# ATmega_3000_14.net
KiCad netlist of a schematic drawn in Altium Designer
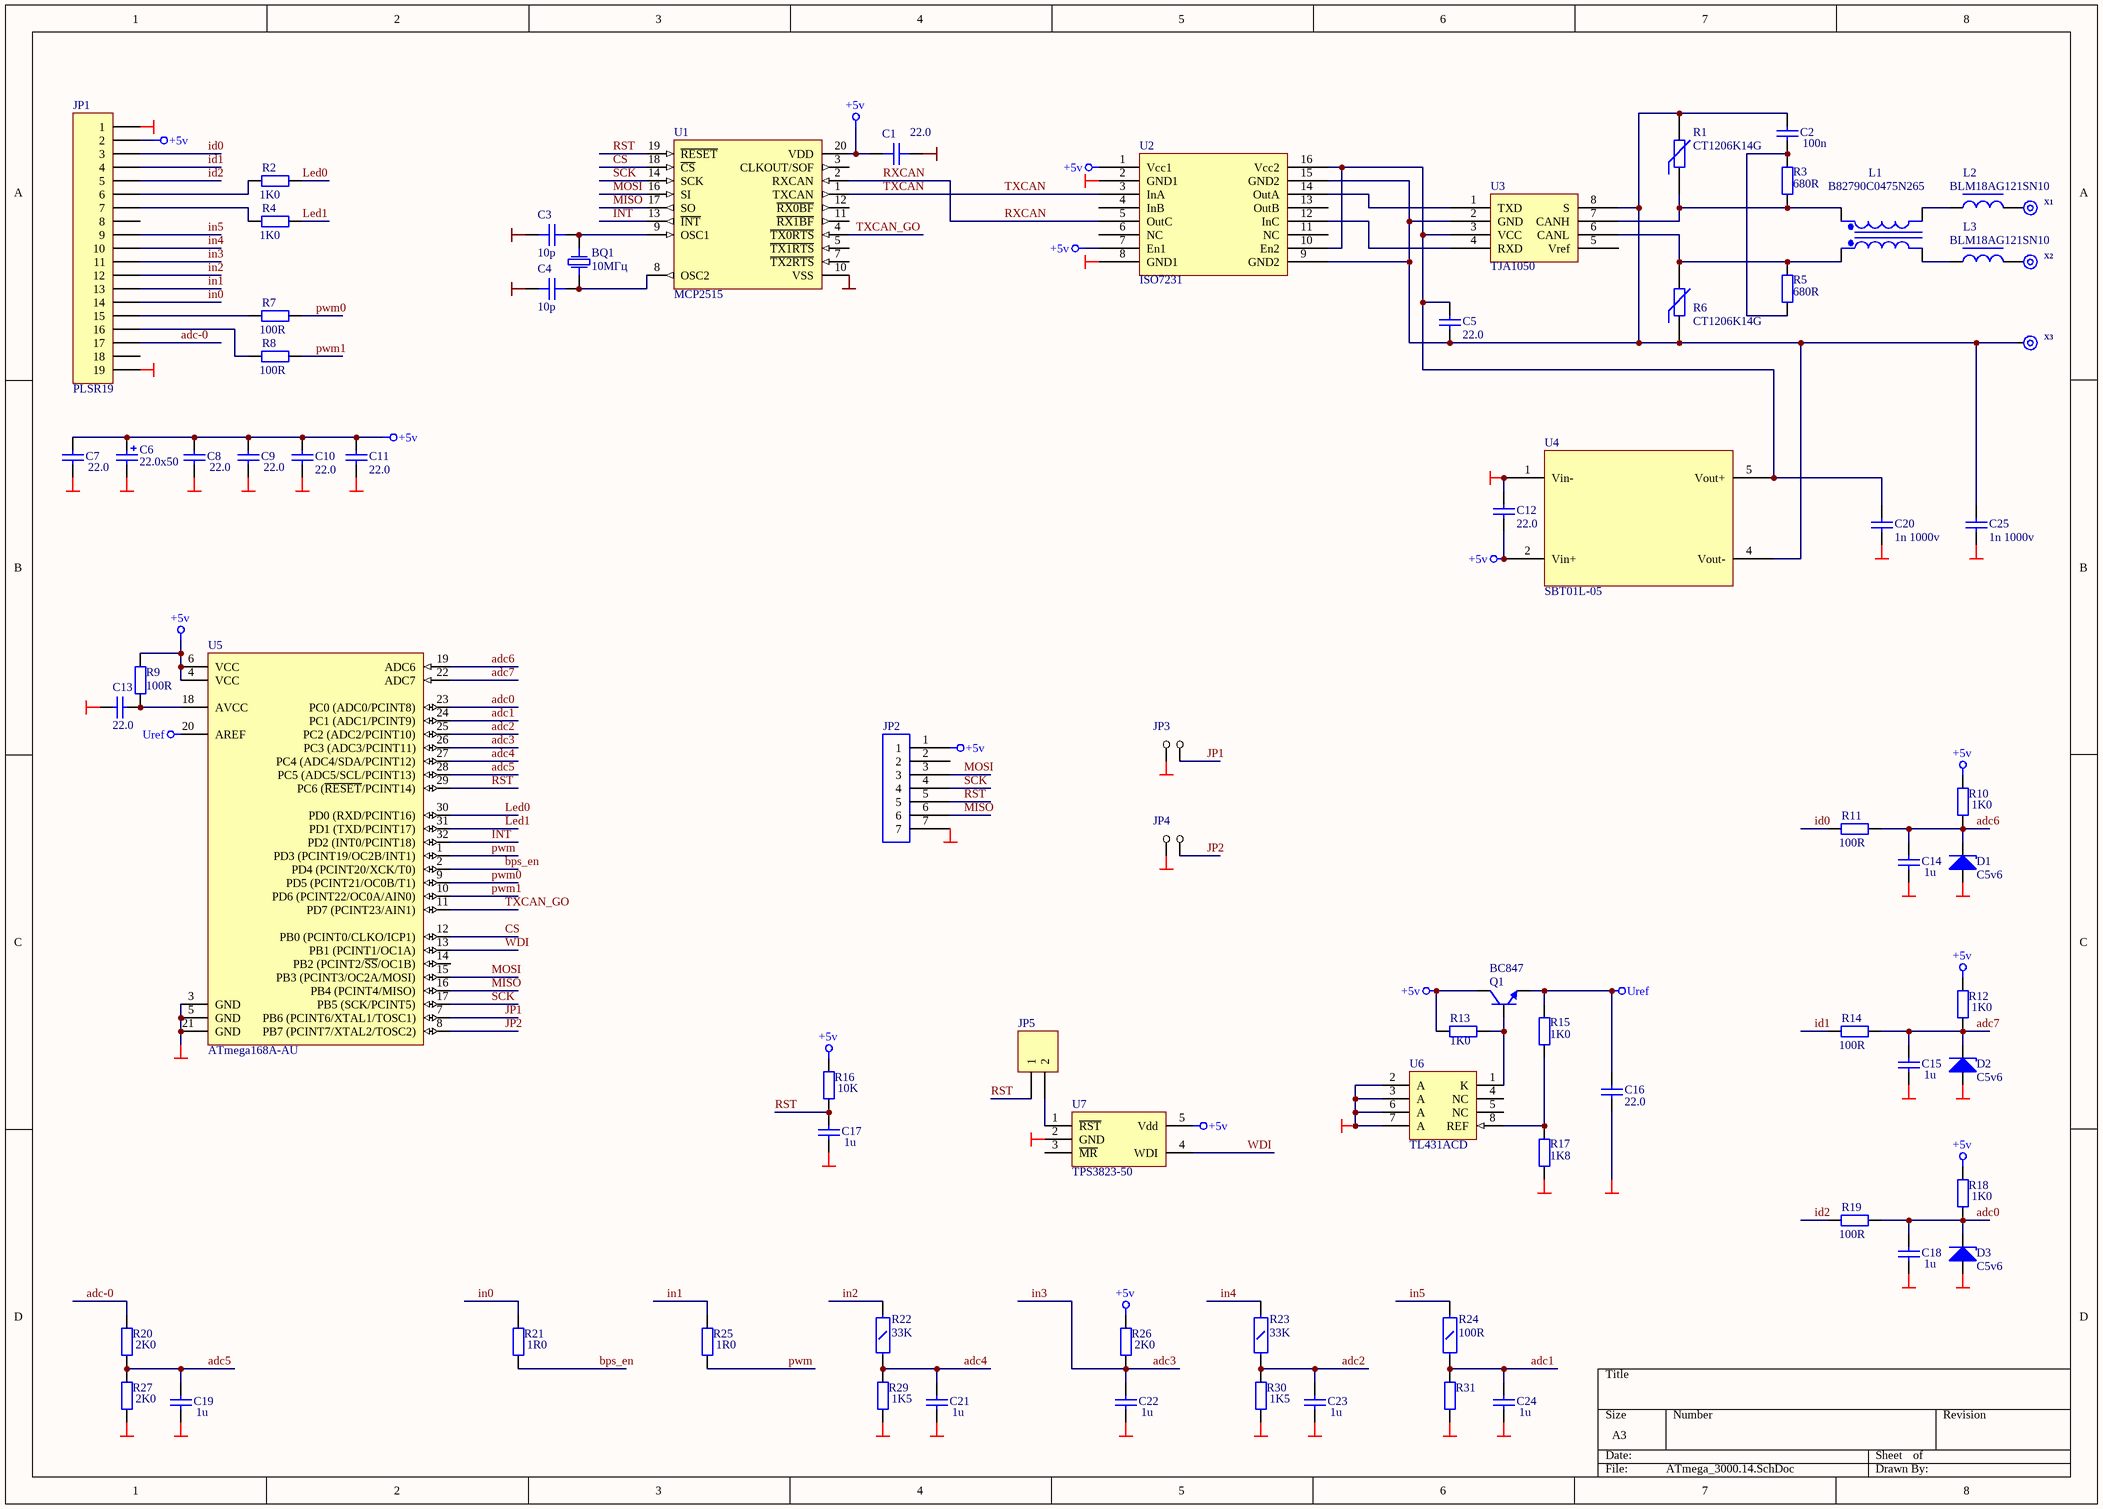
[diagram p0: ATmega_3000.14.SchDoc]

(export (version "E")
  (design (tool "Eeschema 10.0.6"))
  (components
    (comp (ref "BQ1") (value "10МГц") (footprint "HC-49SMD") (libsource (lib "L") (part "BQ")))
    (comp (ref "C1") (value "22.0") (footprint "C_1206") (libsource (lib "C") (part "C_SM_1206")))
    (comp (ref "C2")
      (value "100n")
      (footprint "0603")
      (description "Capacitor (Semiconductor SIM Model)")
      (fields (field (name "MANUFACTURER") "Generic Components") (field (name "PUBLISHER") "Altium Limited"))
      (libsource (lib "Miscellaneous Devices") (part "Cap Semi"))
    )
    (comp (ref "C3") (value "10p") (footprint "0603") (libsource (lib "C") (part "C_SM_1206")))
    (comp (ref "C4") (value "10p") (footprint "0603") (libsource (lib "C") (part "C_SM_1206")))
    (comp (ref "C5")
      (value "22.0")
      (footprint "_1206")
      (description "Capacitor (Semiconductor SIM Model)")
      (fields (field (name "MANUFACTURER") "Generic Components") (field (name "PUBLISHER") "Altium Limited"))
      (libsource (lib "Miscellaneous Devices") (part "Cap Semi"))
    )
    (comp (ref "C6")
      (value "22.0x50")
      (footprint "C_5d_2pad")
      (description "Polarized Capacitor (Radial)")
      (fields (field (name "MANUFACTURER") "Generic Components") (field (name "PUBLISHER") "Altium Limited"))
      (libsource (lib "PAL") (part "Cap Pol1"))
    )
    (comp (ref "C7")
      (value "22.0")
      (footprint "_1206")
      (description "Capacitor (Semiconductor SIM Model)")
      (fields (field (name "MANUFACTURER") "Generic Components") (field (name "PUBLISHER") "Altium Limited"))
      (libsource (lib "Miscellaneous Devices") (part "Cap Semi"))
    )
    (comp (ref "C8")
      (value "22.0")
      (footprint "_1206")
      (description "Capacitor (Semiconductor SIM Model)")
      (fields (field (name "MANUFACTURER") "Generic Components") (field (name "PUBLISHER") "Altium Limited"))
      (libsource (lib "Miscellaneous Devices") (part "Cap Semi"))
    )
    (comp (ref "C9")
      (value "22.0")
      (footprint "_1206")
      (description "Capacitor (Semiconductor SIM Model)")
      (fields (field (name "MANUFACTURER") "Generic Components") (field (name "PUBLISHER") "Altium Limited"))
      (libsource (lib "Miscellaneous Devices") (part "Cap Semi"))
    )
    (comp (ref "C10")
      (value "22.0")
      (footprint "_1206")
      (description "Capacitor (Semiconductor SIM Model)")
      (fields (field (name "MANUFACTURER") "Generic Components") (field (name "PUBLISHER") "Altium Limited"))
      (libsource (lib "Miscellaneous Devices") (part "Cap Semi"))
    )
    (comp (ref "C11")
      (value "22.0")
      (footprint "_1206")
      (description "Capacitor (Semiconductor SIM Model)")
      (fields (field (name "MANUFACTURER") "Generic Components") (field (name "PUBLISHER") "Altium Limited"))
      (libsource (lib "Miscellaneous Devices") (part "Cap Semi"))
    )
    (comp (ref "C12")
      (value "22.0")
      (footprint "_1206")
      (description "Capacitor (Semiconductor SIM Model)")
      (fields (field (name "MANUFACTURER") "Generic Components") (field (name "PUBLISHER") "Altium Limited"))
      (libsource (lib "Miscellaneous Devices") (part "Cap Semi"))
    )
    (comp (ref "C13")
      (value "22.0")
      (footprint "_1206")
      (description "Capacitor (Semiconductor SIM Model)")
      (fields (field (name "MANUFACTURER") "Generic Components") (field (name "PUBLISHER") "Altium Limited"))
      (libsource (lib "Miscellaneous Devices") (part "Cap Semi"))
    )
    (comp (ref "C14")
      (value "1u")
      (footprint "0603")
      (description "Capacitor (Semiconductor SIM Model)")
      (fields (field (name "MANUFACTURER") "Generic Components") (field (name "PUBLISHER") "Altium Limited"))
      (libsource (lib "Miscellaneous Devices") (part "Cap Semi"))
    )
    (comp (ref "C15")
      (value "1u")
      (footprint "0603")
      (description "Capacitor (Semiconductor SIM Model)")
      (fields (field (name "MANUFACTURER") "Generic Components") (field (name "PUBLISHER") "Altium Limited"))
      (libsource (lib "Miscellaneous Devices") (part "Cap Semi"))
    )
    (comp (ref "C16")
      (value "22.0")
      (footprint "_1206")
      (description "Capacitor (Semiconductor SIM Model)")
      (fields (field (name "MANUFACTURER") "Generic Components") (field (name "PUBLISHER") "Altium Limited"))
      (libsource (lib "Miscellaneous Devices") (part "Cap Semi"))
    )
    (comp (ref "C17")
      (value "1u")
      (footprint "0603")
      (description "Capacitor (Semiconductor SIM Model)")
      (fields (field (name "MANUFACTURER") "Generic Components") (field (name "PUBLISHER") "Altium Limited"))
      (libsource (lib "Miscellaneous Devices") (part "Cap Semi"))
    )
    (comp (ref "C18")
      (value "1u")
      (footprint "0603")
      (description "Capacitor (Semiconductor SIM Model)")
      (fields (field (name "MANUFACTURER") "Generic Components") (field (name "PUBLISHER") "Altium Limited"))
      (libsource (lib "Miscellaneous Devices") (part "Cap Semi"))
    )
    (comp (ref "C19")
      (value "1u")
      (footprint "0603")
      (description "Capacitor (Semiconductor SIM Model)")
      (fields (field (name "MANUFACTURER") "Generic Components") (field (name "PUBLISHER") "Altium Limited"))
      (libsource (lib "Miscellaneous Devices") (part "Cap Semi"))
    )
    (comp (ref "C20")
      (value "1n 1000v")
      (footprint "_1206")
      (description "Capacitor (Semiconductor SIM Model)")
      (fields (field (name "MANUFACTURER") "Generic Components") (field (name "PUBLISHER") "Altium Limited"))
      (libsource (lib "Miscellaneous Devices") (part "Cap Semi"))
    )
    (comp (ref "C21")
      (value "1u")
      (footprint "0603")
      (description "Capacitor (Semiconductor SIM Model)")
      (fields (field (name "MANUFACTURER") "Generic Components") (field (name "PUBLISHER") "Altium Limited"))
      (libsource (lib "Miscellaneous Devices") (part "Cap Semi"))
    )
    (comp (ref "C22")
      (value "1u")
      (footprint "0603")
      (description "Capacitor (Semiconductor SIM Model)")
      (fields (field (name "MANUFACTURER") "Generic Components") (field (name "PUBLISHER") "Altium Limited"))
      (libsource (lib "Miscellaneous Devices") (part "Cap Semi"))
    )
    (comp (ref "C23")
      (value "1u")
      (footprint "0603")
      (description "Capacitor (Semiconductor SIM Model)")
      (fields (field (name "MANUFACTURER") "Generic Components") (field (name "PUBLISHER") "Altium Limited"))
      (libsource (lib "Miscellaneous Devices") (part "Cap Semi"))
    )
    (comp (ref "C24")
      (value "1u")
      (footprint "0603")
      (description "Capacitor (Semiconductor SIM Model)")
      (fields (field (name "MANUFACTURER") "Generic Components") (field (name "PUBLISHER") "Altium Limited"))
      (libsource (lib "Miscellaneous Devices") (part "Cap Semi"))
    )
    (comp (ref "C25")
      (value "1n 1000v")
      (footprint "_1206")
      (description "Capacitor (Semiconductor SIM Model)")
      (fields (field (name "MANUFACTURER") "Generic Components") (field (name "PUBLISHER") "Altium Limited"))
      (libsource (lib "Miscellaneous Devices") (part "Cap Semi"))
    )
    (comp (ref "D1")
      (value "C5v6")
      (footprint "SM/D_1406")
      (description "Default Diode")
      (fields (field (name "MANUFACTURER") "Generic Components") (field (name "PUBLISHER") "Altium Limited"))
      (libsource (lib "PAL") (part "Zener"))
    )
    (comp (ref "D2")
      (value "C5v6")
      (footprint "SM/D_1406")
      (description "Default Diode")
      (fields (field (name "MANUFACTURER") "Generic Components") (field (name "PUBLISHER") "Altium Limited"))
      (libsource (lib "PAL") (part "Zener"))
    )
    (comp (ref "D3")
      (value "C5v6")
      (footprint "SM/D_1406")
      (description "Default Diode")
      (fields (field (name "MANUFACTURER") "Generic Components") (field (name "PUBLISHER") "Altium Limited"))
      (libsource (lib "PAL") (part "Zener"))
    )
    (comp (ref "JP1")
      (value "PLSR19")
      (footprint "HDR1X19")
      (description "Header, 19-Pin")
      (fields (field (name "MANUFACTURER") "Generic Components") (field (name "PUBLISHER") "Altium Limited"))
      (libsource (lib "Miscellaneous Connectors") (part "Header 19"))
    )
    (comp (ref "JP2") (value "PLSF-7") (footprint "HDR1X7") (libsource (lib "RAZJEM") (part "PLSF-7")))
    (comp (ref "JP3") (value "JMP") (footprint "HDR1X2") (libsource (lib "RAZJEM") (part "JMP")))
    (comp (ref "JP4") (value "JMP") (footprint "HDR1X2") (libsource (lib "RAZJEM") (part "JMP")))
    (comp (ref "JP5")
      (value "PLS2")
      (footprint "HDR1X2")
      (description "Header, 2-Pin")
      (fields (field (name "MANUFACTURER") "Generic Components") (field (name "PUBLISHER") "Altium Limited"))
      (libsource (lib "Miscellaneous Connectors") (part "Header 2"))
    )
    (comp (ref "L1")
      (value "B82790C0475N265")
      (footprint "B82790")
      (description "Transformer (Coupled Inductor Model)")
      (fields (field (name "PUBLISHER") "Altium Limited"))
      (libsource (lib "Miscellaneous Devices") (part "Trans Cupl"))
    )
    (comp (ref "L2")
      (value "BLM18AG121SN10")
      (footprint "0603")
      (description "L")
      (libsource (lib "L") (part "DR"))
    )
    (comp (ref "L3")
      (value "BLM18AG121SN10")
      (footprint "0603")
      (description "L")
      (libsource (lib "L") (part "DR"))
    )
    (comp (ref "Q1")
      (value "BC847")
      (footprint "SOT23")
      (description "General Purpose Transistor NPN Silicon")
      (fields (field (name "MANUFACTURER") "Motorola") (field (name "PUBLISHER") "Altium Limited"))
      (libsource (lib "PAL") (part "BC847ALT1"))
    )
    (comp (ref "R1")
      (value "CT1206K14G")
      (footprint "1206")
      (description "Varistor (Voltage-Sensitive Resistor)")
      (fields (field (name "MANUFACTURER") "Generic Components") (field (name "PUBLISHER") "Altium Limited"))
      (libsource (lib "Miscellaneous Devices") (part "Res Varistor"))
    )
    (comp (ref "R2")
      (value "1K0")
      (footprint "0603")
      (description "Resistor")
      (fields (field (name "MANUFACTURER") "Generic Components") (field (name "PUBLISHER") "Altium Limited"))
      (libsource (lib "") (part "Res2_2"))
    )
    (comp (ref "R3")
      (value "680R")
      (footprint "0603")
      (description "Resistor")
      (fields (field (name "MANUFACTURER") "Generic Components") (field (name "PUBLISHER") "Altium Limited"))
      (libsource (lib "") (part "Res2_2"))
    )
    (comp (ref "R4")
      (value "1K0")
      (footprint "0603")
      (description "Resistor")
      (fields (field (name "MANUFACTURER") "Generic Components") (field (name "PUBLISHER") "Altium Limited"))
      (libsource (lib "") (part "Res2_2"))
    )
    (comp (ref "R5")
      (value "680R")
      (footprint "0603")
      (description "Resistor")
      (fields (field (name "MANUFACTURER") "Generic Components") (field (name "PUBLISHER") "Altium Limited"))
      (libsource (lib "") (part "Res2_2"))
    )
    (comp (ref "R6")
      (value "CT1206K14G")
      (footprint "1206")
      (description "Varistor (Voltage-Sensitive Resistor)")
      (fields (field (name "MANUFACTURER") "Generic Components") (field (name "PUBLISHER") "Altium Limited"))
      (libsource (lib "Miscellaneous Devices") (part "Res Varistor"))
    )
    (comp (ref "R7")
      (value "100R")
      (footprint "0603")
      (description "Resistor")
      (fields (field (name "MANUFACTURER") "Generic Components") (field (name "PUBLISHER") "Altium Limited"))
      (libsource (lib "") (part "Res2_1"))
    )
    (comp (ref "R8")
      (value "100R")
      (footprint "0603")
      (description "Resistor")
      (fields (field (name "MANUFACTURER") "Generic Components") (field (name "PUBLISHER") "Altium Limited"))
      (libsource (lib "") (part "Res2_1"))
    )
    (comp (ref "R9")
      (value "100R")
      (footprint "0603")
      (description "Resistor")
      (fields (field (name "MANUFACTURER") "Generic Components") (field (name "PUBLISHER") "Altium Limited"))
      (libsource (lib "") (part "Res2_4"))
    )
    (comp (ref "R10")
      (value "1K0")
      (footprint "0603")
      (description "Resistor")
      (fields (field (name "MANUFACTURER") "Generic Components") (field (name "PUBLISHER") "Altium Limited"))
      (libsource (lib "") (part "Res2_3"))
    )
    (comp (ref "R11")
      (value "100R")
      (footprint "0603")
      (description "Resistor")
      (fields (field (name "MANUFACTURER") "Generic Components") (field (name "PUBLISHER") "Altium Limited"))
      (libsource (lib "") (part "Res2_1"))
    )
    (comp (ref "R12")
      (value "1K0")
      (footprint "0603")
      (description "Resistor")
      (fields (field (name "MANUFACTURER") "Generic Components") (field (name "PUBLISHER") "Altium Limited"))
      (libsource (lib "") (part "Res2_3"))
    )
    (comp (ref "R13")
      (value "1K0")
      (footprint "0603")
      (description "Resistor")
      (fields (field (name "MANUFACTURER") "Generic Components") (field (name "PUBLISHER") "Altium Limited"))
      (libsource (lib "") (part "Res2_5"))
    )
    (comp (ref "R14")
      (value "100R")
      (footprint "0603")
      (description "Resistor")
      (fields (field (name "MANUFACTURER") "Generic Components") (field (name "PUBLISHER") "Altium Limited"))
      (libsource (lib "") (part "Res2_1"))
    )
    (comp (ref "R15")
      (value "1K0")
      (footprint "0603")
      (description "Resistor")
      (fields (field (name "MANUFACTURER") "Generic Components") (field (name "PUBLISHER") "Altium Limited"))
      (libsource (lib "") (part "Res2_2"))
    )
    (comp (ref "R16")
      (value "10K")
      (footprint "0603")
      (description "Resistor")
      (fields (field (name "MANUFACTURER") "Generic Components") (field (name "PUBLISHER") "Altium Limited"))
      (libsource (lib "") (part "Res2_3"))
    )
    (comp (ref "R17")
      (value "1K8")
      (footprint "0603")
      (description "Resistor")
      (fields (field (name "MANUFACTURER") "Generic Components") (field (name "PUBLISHER") "Altium Limited"))
      (libsource (lib "") (part "Res2_2"))
    )
    (comp (ref "R18")
      (value "1K0")
      (footprint "0603")
      (description "Resistor")
      (fields (field (name "MANUFACTURER") "Generic Components") (field (name "PUBLISHER") "Altium Limited"))
      (libsource (lib "") (part "Res2_3"))
    )
    (comp (ref "R19")
      (value "100R")
      (footprint "0603")
      (description "Resistor")
      (fields (field (name "MANUFACTURER") "Generic Components") (field (name "PUBLISHER") "Altium Limited"))
      (libsource (lib "") (part "Res2_1"))
    )
    (comp (ref "R20")
      (value "2K0")
      (footprint "0603")
      (description "Resistor")
      (fields (field (name "MANUFACTURER") "Generic Components") (field (name "PUBLISHER") "Altium Limited"))
      (libsource (lib "Miscellaneous Devices") (part "Res2"))
    )
    (comp (ref "R21")
      (value "1R0")
      (footprint "0603")
      (description "Resistor")
      (fields (field (name "MANUFACTURER") "Generic Components") (field (name "PUBLISHER") "Altium Limited"))
      (libsource (lib "Miscellaneous Devices") (part "Res2"))
    )
    (comp (ref "R22") (value "33K") (footprint "1206") (libsource (lib "resistor") (part "R_1206")))
    (comp (ref "R23") (value "33K") (footprint "1206") (libsource (lib "resistor") (part "R_1206")))
    (comp (ref "R24") (value "100R") (footprint "1206") (libsource (lib "resistor") (part "R_1206")))
    (comp (ref "R25")
      (value "1R0")
      (footprint "0603")
      (description "Resistor")
      (fields (field (name "MANUFACTURER") "Generic Components") (field (name "PUBLISHER") "Altium Limited"))
      (libsource (lib "Miscellaneous Devices") (part "Res2"))
    )
    (comp (ref "R26")
      (value "2K0")
      (footprint "0603")
      (description "Resistor")
      (fields (field (name "MANUFACTURER") "Generic Components") (field (name "PUBLISHER") "Altium Limited"))
      (libsource (lib "Miscellaneous Devices") (part "Res2"))
    )
    (comp (ref "R27")
      (value "2K0")
      (footprint "0603")
      (description "Resistor")
      (fields (field (name "MANUFACTURER") "Generic Components") (field (name "PUBLISHER") "Altium Limited"))
      (libsource (lib "Miscellaneous Devices") (part "Res2"))
    )
    (comp (ref "R29")
      (value "1K5")
      (footprint "0603")
      (description "Resistor")
      (fields (field (name "MANUFACTURER") "Generic Components") (field (name "PUBLISHER") "Altium Limited"))
      (libsource (lib "Miscellaneous Devices") (part "Res2"))
    )
    (comp (ref "R30")
      (value "1K5")
      (footprint "0603")
      (description "Resistor")
      (fields (field (name "MANUFACTURER") "Generic Components") (field (name "PUBLISHER") "Altium Limited"))
      (libsource (lib "Miscellaneous Devices") (part "Res2"))
    )
    (comp (ref "R31")
      (value "~")
      (footprint "0603")
      (description "Resistor")
      (fields (field (name "MANUFACTURER") "Generic Components") (field (name "PUBLISHER") "Altium Limited"))
      (libsource (lib "Miscellaneous Devices") (part "Res2"))
    )
    (comp (ref "U1")
      (value "MCP2515")
      (footprint "TSSOP-ST20_N")
      (description "Stand-Alone CAN Controller With SPI Interface, 20-Pin TSSOP, Industrial Temperature")
      (libsource (lib "CHIP") (part "MCP2515"))
    )
    (comp (ref "U2") (value "ISO7231") (footprint "DW16_N") (libsource (lib "PAL") (part "ISO7231")))
    (comp (ref "U3")
      (value "TJA1050")
      (footprint "SOIC-8-1.27-L.200")
      (libsource (lib "PAL") (part "TJA1050"))
    )
    (comp (ref "U4") (value "SBT01L-05") (footprint "SBT01L") (libsource (lib "PAL") (part "SBT01L")))
    (comp (ref "U5")
      (value "ATmega168A-AU")
      (footprint "32A_N")
      (fields (field (name "PUBLISHER") "Altium Limited"))
      (libsource (lib "Atmel Microcontroller 8-Bit megaAVR") (part "ATmega168A-AU"))
    )
    (comp (ref "U6")
      (value "TL431ACD")
      (footprint "SO-G8")
      (description "Programmable Precision Reference")
      (fields (field (name "MANUFACTURER") "Motorola") (field (name "PUBLISHER") "Altium Limited"))
      (libsource (lib "Motorola Power Management Voltage Reference") (part "TL431ACD"))
    )
    (comp (ref "U7")
      (value "TPS3823-50")
      (footprint "SO-G5/P.95")
      (description "Reset IC")
      (fields
        (field (name "MANUFACTURER") "National Semiconductor")
        (field (name "PUBLISHER") "Altium Limited")
      )
      (libsource (lib "PAL") (part "TPS3823"))
    )
    (comp (ref "X1")
      (value "~")
      (footprint "PIN2R")
      (description "Socket")
      (fields (field (name "MANUFACTURER") "Generic Components") (field (name "PUBLISHER") "Altium Limited"))
      (libsource (lib "PAL") (part "Socket_Ring"))
    )
    (comp (ref "X2")
      (value "~")
      (footprint "PIN2R")
      (description "Socket")
      (fields (field (name "MANUFACTURER") "Generic Components") (field (name "PUBLISHER") "Altium Limited"))
      (libsource (lib "PAL") (part "Socket_Ring"))
    )
    (comp (ref "X3")
      (value "~")
      (footprint "PIN2R")
      (description "Socket")
      (fields (field (name "MANUFACTURER") "Generic Components") (field (name "PUBLISHER") "Altium Limited"))
      (libsource (lib "PAL") (part "Socket_Ring"))
    )
  )
  (nets
    (net (code "1") (name "+5v") (class "Default")
      (node (ref "C1") (pin "2") (pinfunction "2_2") (pintype "passive"))
      (node (ref "C10") (pin "1") (pinfunction "1_1") (pintype "passive"))
      (node (ref "C11") (pin "1") (pinfunction "1_1") (pintype "passive"))
      (node (ref "C12") (pin "2") (pinfunction "2_2") (pintype "passive"))
      (node (ref "C6") (pin "+") (pinfunction "+_+") (pintype "passive"))
      (node (ref "C7") (pin "2") (pinfunction "2_2") (pintype "passive"))
      (node (ref "C8") (pin "2") (pinfunction "2_2") (pintype "passive"))
      (node (ref "C9") (pin "2") (pinfunction "2_2") (pintype "passive"))
      (node (ref "JP1") (pin "2") (pinfunction "2_2") (pintype "passive"))
      (node (ref "JP2") (pin "1") (pinfunction "1_1") (pintype "passive"))
      (node (ref "Q1") (pin "2") (pinfunction "C_2") (pintype "passive"))
      (node (ref "R10") (pin "1") (pinfunction "1_1") (pintype "passive"))
      (node (ref "R12") (pin "1") (pinfunction "1_1") (pintype "passive"))
      (node (ref "R13") (pin "1") (pinfunction "1_1") (pintype "passive"))
      (node (ref "R16") (pin "1") (pinfunction "1_1") (pintype "passive"))
      (node (ref "R18") (pin "1") (pinfunction "1_1") (pintype "passive"))
      (node (ref "R26") (pin "2") (pinfunction "2_2") (pintype "passive"))
      (node (ref "R9") (pin "1") (pinfunction "1_1") (pintype "passive"))
      (node (ref "U1") (pin "20") (pinfunction "VDD_20") (pintype "power_in"))
      (node (ref "U2") (pin "1") (pinfunction "Vcc1_1") (pintype "passive"))
      (node (ref "U2") (pin "7") (pinfunction "En1_7") (pintype "passive"))
      (node (ref "U4") (pin "2") (pinfunction "Vin+_2") (pintype "passive"))
      (node (ref "U5") (pin "4") (pinfunction "VCC_4") (pintype "power_in"))
      (node (ref "U5") (pin "6") (pinfunction "VCC_6") (pintype "power_in"))
      (node (ref "U7") (pin "5") (pinfunction "Vdd_5") (pintype "power_in"))
    )
    (net (code "2") (name "/CS") (class "Default")
      (node (ref "U1") (pin "18") (pinfunction "~{CS}_18") (pintype "input"))
      (node (ref "U5") (pin "12") (pinfunction "PB0_(PCINT0/CLKO/ICP1)_12") (pintype "bidirectional"))
    )
    (net (code "3") (name "/INT") (class "Default")
      (node (ref "U1") (pin "13") (pinfunction "~{INT}_13") (pintype "output"))
      (node (ref "U5") (pin "32") (pinfunction "PD2_(INT0/PCINT18)_32") (pintype "bidirectional"))
    )
    (net (code "4") (name "/JP1") (class "Default")
      (node (ref "JP3") (pin "2") (pinfunction "2_2") (pintype "passive"))
      (node (ref "U5") (pin "7") (pinfunction "PB6_(PCINT6/XTAL1/TOSC1)_7") (pintype "bidirectional"))
    )
    (net (code "5") (name "/JP2") (class "Default")
      (node (ref "JP4") (pin "2") (pinfunction "2_2") (pintype "passive"))
      (node (ref "U5") (pin "8") (pinfunction "PB7_(PCINT7/XTAL2/TOSC2)_8") (pintype "bidirectional"))
    )
    (net (code "6") (name "/Led0") (class "Default")
      (node (ref "R2") (pin "2") (pinfunction "2_2") (pintype "passive"))
      (node (ref "U5") (pin "30") (pinfunction "PD0_(RXD/PCINT16)_30") (pintype "bidirectional"))
    )
    (net (code "7") (name "/Led1") (class "Default")
      (node (ref "R4") (pin "2") (pinfunction "2_2") (pintype "passive"))
      (node (ref "U5") (pin "31") (pinfunction "PD1_(TXD/PCINT17)_31") (pintype "bidirectional"))
    )
    (net (code "8") (name "/MISO") (class "Default")
      (node (ref "JP2") (pin "6") (pinfunction "6_6") (pintype "passive"))
      (node (ref "U1") (pin "17") (pinfunction "SO_17") (pintype "output"))
      (node (ref "U5") (pin "16") (pinfunction "PB4_(PCINT4/MISO)_16") (pintype "bidirectional"))
    )
    (net (code "9") (name "/MOSI") (class "Default")
      (node (ref "JP2") (pin "3") (pinfunction "3_3") (pintype "passive"))
      (node (ref "U1") (pin "16") (pinfunction "SI_16") (pintype "input"))
      (node (ref "U5") (pin "15") (pinfunction "PB3_(PCINT3/OC2A/MOSI)_15") (pintype "bidirectional"))
    )
    (net (code "10") (name "/RST") (class "Default")
      (node (ref "C17") (pin "2") (pinfunction "2_2") (pintype "passive"))
      (node (ref "JP2") (pin "5") (pinfunction "5_5") (pintype "passive"))
      (node (ref "JP5") (pin "1") (pinfunction "1_1") (pintype "passive"))
      (node (ref "R16") (pin "2") (pinfunction "2_2") (pintype "passive"))
      (node (ref "U1") (pin "19") (pinfunction "~{RESET}_19") (pintype "input"))
      (node (ref "U5") (pin "29") (pinfunction "PC6_(~{RESET}/PCINT14)_29") (pintype "bidirectional"))
    )
    (net (code "11") (name "/RXCAN") (class "Default")
      (node (ref "U1") (pin "2") (pinfunction "RXCAN_2") (pintype "input"))
      (node (ref "U2") (pin "5") (pinfunction "OutC_5") (pintype "passive"))
    )
    (net (code "12") (name "/SCK") (class "Default")
      (node (ref "JP2") (pin "4") (pinfunction "4_4") (pintype "passive"))
      (node (ref "U1") (pin "14") (pinfunction "SCK_14") (pintype "input"))
      (node (ref "U5") (pin "17") (pinfunction "PB5_(SCK/PCINT5)_17") (pintype "bidirectional"))
    )
    (net (code "13") (name "/TXCAN") (class "Default")
      (node (ref "U1") (pin "1") (pinfunction "TXCAN_1") (pintype "output"))
      (node (ref "U2") (pin "3") (pinfunction "InA_3") (pintype "passive"))
    )
    (net (code "14") (name "/TXCAN_GO") (class "Default")
      (node (ref "U1") (pin "4") (pinfunction "~{TX0RTS}_4") (pintype "input"))
      (node (ref "U5") (pin "11") (pinfunction "PD7_(PCINT23/AIN1)_11") (pintype "bidirectional"))
    )
    (net (code "15") (name "/WDI") (class "Default")
      (node (ref "U5") (pin "13") (pinfunction "PB1_(PCINT1/OC1A)_13") (pintype "bidirectional"))
      (node (ref "U7") (pin "4") (pinfunction "WDI_4") (pintype "passive"))
    )
    (net (code "16") (name "/adc-0") (class "Default")
      (node (ref "JP1") (pin "17") (pinfunction "17_17") (pintype "passive"))
      (node (ref "R20") (pin "2") (pinfunction "2_2") (pintype "passive"))
    )
    (net (code "17") (name "/adc0") (class "Default")
      (node (ref "C18") (pin "2") (pinfunction "2_2") (pintype "passive"))
      (node (ref "D3") (pin "-") (pinfunction "-_-") (pintype "passive"))
      (node (ref "R18") (pin "2") (pinfunction "2_2") (pintype "passive"))
      (node (ref "R19") (pin "1") (pinfunction "1_1") (pintype "passive"))
      (node (ref "U5") (pin "23") (pinfunction "PC0_(ADC0/PCINT8)_23") (pintype "bidirectional"))
    )
    (net (code "18") (name "/adc1") (class "Default")
      (node (ref "C24") (pin "2") (pinfunction "2_2") (pintype "passive"))
      (node (ref "R24") (pin "2") (pinfunction "2_2") (pintype "passive"))
      (node (ref "R31") (pin "2") (pinfunction "2_2") (pintype "passive"))
      (node (ref "U5") (pin "24") (pinfunction "PC1_(ADC1/PCINT9)_24") (pintype "bidirectional"))
    )
    (net (code "19") (name "/adc2") (class "Default")
      (node (ref "C23") (pin "2") (pinfunction "2_2") (pintype "passive"))
      (node (ref "R23") (pin "2") (pinfunction "2_2") (pintype "passive"))
      (node (ref "R30") (pin "2") (pinfunction "2_2") (pintype "passive"))
      (node (ref "U5") (pin "25") (pinfunction "PC2_(ADC2/PCINT10)_25") (pintype "bidirectional"))
    )
    (net (code "20") (name "/adc3") (class "Default")
      (node (ref "C22") (pin "2") (pinfunction "2_2") (pintype "passive"))
      (node (ref "JP1") (pin "11") (pinfunction "11_11") (pintype "passive"))
      (node (ref "R26") (pin "1") (pinfunction "1_1") (pintype "passive"))
      (node (ref "U5") (pin "26") (pinfunction "PC3_(ADC3/PCINT11)_26") (pintype "bidirectional"))
    )
    (net (code "21") (name "/adc4") (class "Default")
      (node (ref "C21") (pin "2") (pinfunction "2_2") (pintype "passive"))
      (node (ref "R22") (pin "2") (pinfunction "2_2") (pintype "passive"))
      (node (ref "R29") (pin "2") (pinfunction "2_2") (pintype "passive"))
      (node (ref "U5") (pin "27") (pinfunction "PC4_(ADC4/SDA/PCINT12)_27") (pintype "bidirectional"))
    )
    (net (code "22") (name "/adc5") (class "Default")
      (node (ref "C19") (pin "2") (pinfunction "2_2") (pintype "passive"))
      (node (ref "R20") (pin "1") (pinfunction "1_1") (pintype "passive"))
      (node (ref "R27") (pin "2") (pinfunction "2_2") (pintype "passive"))
      (node (ref "U5") (pin "28") (pinfunction "PC5_(ADC5/SCL/PCINT13)_28") (pintype "bidirectional"))
    )
    (net (code "23") (name "/adc6") (class "Default")
      (node (ref "C14") (pin "2") (pinfunction "2_2") (pintype "passive"))
      (node (ref "D1") (pin "-") (pinfunction "-_-") (pintype "passive"))
      (node (ref "R10") (pin "2") (pinfunction "2_2") (pintype "passive"))
      (node (ref "R11") (pin "1") (pinfunction "1_1") (pintype "passive"))
      (node (ref "U5") (pin "19") (pinfunction "ADC6_19") (pintype "input"))
    )
    (net (code "24") (name "/adc7") (class "Default")
      (node (ref "C15") (pin "2") (pinfunction "2_2") (pintype "passive"))
      (node (ref "D2") (pin "-") (pinfunction "-_-") (pintype "passive"))
      (node (ref "R12") (pin "2") (pinfunction "2_2") (pintype "passive"))
      (node (ref "R14") (pin "1") (pinfunction "1_1") (pintype "passive"))
      (node (ref "U5") (pin "22") (pinfunction "ADC7_22") (pintype "input"))
    )
    (net (code "25") (name "/bps_en") (class "Default")
      (node (ref "R21") (pin "1") (pinfunction "1_1") (pintype "passive"))
      (node (ref "U5") (pin "2") (pinfunction "PD4_(PCINT20/XCK/T0)_2") (pintype "bidirectional"))
    )
    (net (code "26") (name "/id0") (class "Default")
      (node (ref "JP1") (pin "3") (pinfunction "3_3") (pintype "passive"))
      (node (ref "R11") (pin "2") (pinfunction "2_2") (pintype "passive"))
    )
    (net (code "27") (name "/id1") (class "Default")
      (node (ref "JP1") (pin "4") (pinfunction "4_4") (pintype "passive"))
      (node (ref "R14") (pin "2") (pinfunction "2_2") (pintype "passive"))
    )
    (net (code "28") (name "/id2") (class "Default")
      (node (ref "JP1") (pin "5") (pinfunction "5_5") (pintype "passive"))
      (node (ref "R19") (pin "2") (pinfunction "2_2") (pintype "passive"))
    )
    (net (code "29") (name "/in0") (class "Default")
      (node (ref "JP1") (pin "14") (pinfunction "14_14") (pintype "passive"))
      (node (ref "R21") (pin "2") (pinfunction "2_2") (pintype "passive"))
    )
    (net (code "30") (name "/in1") (class "Default")
      (node (ref "JP1") (pin "13") (pinfunction "13_13") (pintype "passive"))
      (node (ref "R25") (pin "2") (pinfunction "2_2") (pintype "passive"))
    )
    (net (code "31") (name "/in2") (class "Default")
      (node (ref "JP1") (pin "12") (pinfunction "12_12") (pintype "passive"))
      (node (ref "R22") (pin "1") (pinfunction "1_1") (pintype "passive"))
    )
    (net (code "32") (name "/in4") (class "Default")
      (node (ref "JP1") (pin "10") (pinfunction "10_10") (pintype "passive"))
      (node (ref "R23") (pin "1") (pinfunction "1_1") (pintype "passive"))
    )
    (net (code "33") (name "/in5") (class "Default")
      (node (ref "JP1") (pin "9") (pinfunction "9_9") (pintype "passive"))
      (node (ref "R24") (pin "1") (pinfunction "1_1") (pintype "passive"))
    )
    (net (code "34") (name "/pwm") (class "Default")
      (node (ref "R25") (pin "1") (pinfunction "1_1") (pintype "passive"))
      (node (ref "U5") (pin "1") (pinfunction "PD3_(PCINT19/OC2B/INT1)_1") (pintype "bidirectional"))
    )
    (net (code "35") (name "/pwm0") (class "Default")
      (node (ref "R7") (pin "1") (pinfunction "1_1") (pintype "passive"))
      (node (ref "U5") (pin "9") (pinfunction "PD5_(PCINT21/OC0B/T1)_9") (pintype "bidirectional"))
    )
    (net (code "36") (name "/pwm1") (class "Default")
      (node (ref "R8") (pin "1") (pinfunction "1_1") (pintype "passive"))
      (node (ref "U5") (pin "10") (pinfunction "PD6_(PCINT22/OC0A/AIN0)_10") (pintype "bidirectional"))
    )
    (net (code "37") (name "GND") (class "Default")
      (node (ref "C1") (pin "1") (pinfunction "1_1") (pintype "passive"))
      (node (ref "C10") (pin "2") (pinfunction "2_2") (pintype "passive"))
      (node (ref "C11") (pin "2") (pinfunction "2_2") (pintype "passive"))
      (node (ref "C12") (pin "1") (pinfunction "1_1") (pintype "passive"))
      (node (ref "C13") (pin "1") (pinfunction "1_1") (pintype "passive"))
      (node (ref "C14") (pin "1") (pinfunction "1_1") (pintype "passive"))
      (node (ref "C15") (pin "1") (pinfunction "1_1") (pintype "passive"))
      (node (ref "C16") (pin "1") (pinfunction "1_1") (pintype "passive"))
      (node (ref "C17") (pin "1") (pinfunction "1_1") (pintype "passive"))
      (node (ref "C18") (pin "1") (pinfunction "1_1") (pintype "passive"))
      (node (ref "C19") (pin "1") (pinfunction "1_1") (pintype "passive"))
      (node (ref "C20") (pin "2") (pinfunction "2_2") (pintype "passive"))
      (node (ref "C21") (pin "1") (pinfunction "1_1") (pintype "passive"))
      (node (ref "C22") (pin "1") (pinfunction "1_1") (pintype "passive"))
      (node (ref "C23") (pin "1") (pinfunction "1_1") (pintype "passive"))
      (node (ref "C24") (pin "1") (pinfunction "1_1") (pintype "passive"))
      (node (ref "C25") (pin "2") (pinfunction "2_2") (pintype "passive"))
      (node (ref "C3") (pin "1") (pinfunction "1_1") (pintype "passive"))
      (node (ref "C4") (pin "1") (pinfunction "1_1") (pintype "passive"))
      (node (ref "C6") (pin "-") (pinfunction "-_-") (pintype "passive"))
      (node (ref "C7") (pin "1") (pinfunction "1_1") (pintype "passive"))
      (node (ref "C8") (pin "1") (pinfunction "1_1") (pintype "passive"))
      (node (ref "C9") (pin "1") (pinfunction "1_1") (pintype "passive"))
      (node (ref "D1") (pin "+") (pinfunction "+_+") (pintype "passive"))
      (node (ref "D2") (pin "+") (pinfunction "+_+") (pintype "passive"))
      (node (ref "D3") (pin "+") (pinfunction "+_+") (pintype "passive"))
      (node (ref "JP1") (pin "1") (pinfunction "1_1") (pintype "passive"))
      (node (ref "JP1") (pin "19") (pinfunction "19_19") (pintype "passive"))
      (node (ref "JP2") (pin "7") (pinfunction "7_7") (pintype "passive"))
      (node (ref "JP3") (pin "1") (pinfunction "1_1") (pintype "passive"))
      (node (ref "JP4") (pin "1") (pinfunction "1_1") (pintype "passive"))
      (node (ref "R17") (pin "1") (pinfunction "1_1") (pintype "passive"))
      (node (ref "R27") (pin "1") (pinfunction "1_1") (pintype "passive"))
      (node (ref "R29") (pin "1") (pinfunction "1_1") (pintype "passive"))
      (node (ref "R30") (pin "1") (pinfunction "1_1") (pintype "passive"))
      (node (ref "R31") (pin "1") (pinfunction "1_1") (pintype "passive"))
      (node (ref "U1") (pin "10") (pinfunction "VSS_10") (pintype "power_in"))
      (node (ref "U2") (pin "2") (pinfunction "GND1_2") (pintype "passive"))
      (node (ref "U2") (pin "8") (pinfunction "GND1_8") (pintype "passive"))
      (node (ref "U4") (pin "1") (pinfunction "Vin-_1") (pintype "passive"))
      (node (ref "U5") (pin "21") (pinfunction "GND_21") (pintype "power_in"))
      (node (ref "U5") (pin "3") (pinfunction "GND_3") (pintype "power_in"))
      (node (ref "U5") (pin "5") (pinfunction "GND_5") (pintype "power_in"))
      (node (ref "U6") (pin "2") (pinfunction "A_2") (pintype "passive"))
      (node (ref "U6") (pin "3") (pinfunction "A_3") (pintype "passive"))
      (node (ref "U6") (pin "6") (pinfunction "A_6") (pintype "passive"))
      (node (ref "U6") (pin "7") (pinfunction "A_7") (pintype "passive"))
      (node (ref "U7") (pin "2") (pinfunction "GND_2") (pintype "power_in"))
    )
    (net (code "38") (name "Net-(C2-Pad1)") (class "Default")
      (node (ref "C2") (pin "1") (pinfunction "1_1") (pintype "passive"))
      (node (ref "R3") (pin "2") (pinfunction "2_2") (pintype "passive"))
      (node (ref "R5") (pin "1") (pinfunction "1_1") (pintype "passive"))
    )
    (net (code "39") (name "Net-(JP1-Pad6)") (class "Default")
      (node (ref "JP1") (pin "6") (pinfunction "6_6") (pintype "passive"))
      (node (ref "R2") (pin "1") (pinfunction "1_1") (pintype "passive"))
    )
    (net (code "40") (name "Net-(JP1-Pad7)") (class "Default")
      (node (ref "JP1") (pin "7") (pinfunction "7_7") (pintype "passive"))
      (node (ref "R4") (pin "1") (pinfunction "1_1") (pintype "passive"))
    )
    (net (code "41") (name "Net-(JP1-Pad15)") (class "Default")
      (node (ref "JP1") (pin "15") (pinfunction "15_15") (pintype "passive"))
      (node (ref "R7") (pin "2") (pinfunction "2_2") (pintype "passive"))
    )
    (net (code "42") (name "Net-(JP1-Pad16)") (class "Default")
      (node (ref "JP1") (pin "16") (pinfunction "16_16") (pintype "passive"))
      (node (ref "R8") (pin "2") (pinfunction "2_2") (pintype "passive"))
    )
    (net (code "43") (name "Net-(L1-Pri+)") (class "Default")
      (node (ref "L1") (pin "1") (pinfunction "Pri+_1") (pintype "passive"))
      (node (ref "R1") (pin "1") (pinfunction "1_1") (pintype "passive"))
      (node (ref "R3") (pin "1") (pinfunction "1_1") (pintype "passive"))
      (node (ref "U3") (pin "7") (pinfunction "CANH_7") (pintype "passive"))
    )
    (net (code "44") (name "Net-(L1-Pri-)") (class "Default")
      (node (ref "L1") (pin "4") (pinfunction "Pri-_4") (pintype "passive"))
      (node (ref "L2") (pin "1") (pinfunction "1_1") (pintype "passive"))
    )
    (net (code "45") (name "Net-(L1-Sec+)") (class "Default")
      (node (ref "L1") (pin "2") (pinfunction "Sec+_2") (pintype "passive"))
      (node (ref "R5") (pin "2") (pinfunction "2_2") (pintype "passive"))
      (node (ref "R6") (pin "2") (pinfunction "2_2") (pintype "passive"))
      (node (ref "U3") (pin "6") (pinfunction "CANL_6") (pintype "passive"))
    )
    (net (code "46") (name "Net-(L1-Sec-)") (class "Default")
      (node (ref "L1") (pin "3") (pinfunction "Sec-_3") (pintype "passive"))
      (node (ref "L3") (pin "1") (pinfunction "1_1") (pintype "passive"))
    )
    (net (code "47") (name "Net-(L2-Pad2)") (class "Default")
      (node (ref "L2") (pin "2") (pinfunction "2_2") (pintype "passive"))
      (node (ref "X1") (pin "1") (pinfunction "1_1") (pintype "passive"))
    )
    (net (code "48") (name "Net-(L3-Pad2)") (class "Default")
      (node (ref "L3") (pin "2") (pinfunction "2_2") (pintype "passive"))
      (node (ref "X2") (pin "1") (pinfunction "1_1") (pintype "passive"))
    )
    (net (code "49") (name "Net-(Q1-B)") (class "Default")
      (node (ref "Q1") (pin "1") (pinfunction "B_1") (pintype "passive"))
      (node (ref "R13") (pin "2") (pinfunction "2_2") (pintype "passive"))
      (node (ref "U6") (pin "1") (pinfunction "K_1") (pintype "passive"))
    )
    (net (code "50") (name "Net-(U1-OSC1)") (class "Default")
      (node (ref "BQ1") (pin "1") (pinfunction "1_1") (pintype "passive"))
      (node (ref "C3") (pin "2") (pinfunction "2_2") (pintype "passive"))
      (node (ref "U1") (pin "9") (pinfunction "OSC1_9") (pintype "input"))
    )
    (net (code "51") (name "Net-(U1-OSC2)") (class "Default")
      (node (ref "BQ1") (pin "2") (pinfunction "2_2") (pintype "passive"))
      (node (ref "C4") (pin "2") (pinfunction "2_2") (pintype "passive"))
      (node (ref "U1") (pin "8") (pinfunction "OSC2_8") (pintype "output"))
    )
    (net (code "52") (name "Net-(U2-En2)") (class "Default")
      (node (ref "C20") (pin "1") (pinfunction "1_1") (pintype "passive"))
      (node (ref "C5") (pin "1") (pinfunction "1_1") (pintype "passive"))
      (node (ref "U2") (pin "10") (pinfunction "En2_10") (pintype "passive"))
      (node (ref "U2") (pin "16") (pinfunction "Vcc2_16") (pintype "passive"))
      (node (ref "U3") (pin "3") (pinfunction "VCC_3") (pintype "passive"))
      (node (ref "U4") (pin "5") (pinfunction "Vout+_5") (pintype "passive"))
    )
    (net (code "53") (name "Net-(U2-InC)") (class "Default")
      (node (ref "U2") (pin "12") (pinfunction "InC_12") (pintype "passive"))
      (node (ref "U3") (pin "4") (pinfunction "RXD_4") (pintype "passive"))
    )
    (net (code "54") (name "Net-(U2-OutA)") (class "Default")
      (node (ref "U2") (pin "14") (pinfunction "OutA_14") (pintype "passive"))
      (node (ref "U3") (pin "1") (pinfunction "TXD_1") (pintype "passive"))
    )
    (net (code "55") (name "Net-(U3-GND)") (class "Default")
      (node (ref "C2") (pin "2") (pinfunction "2_2") (pintype "passive"))
      (node (ref "C25") (pin "1") (pinfunction "1_1") (pintype "passive"))
      (node (ref "C5") (pin "2") (pinfunction "2_2") (pintype "passive"))
      (node (ref "R1") (pin "2") (pinfunction "2_2") (pintype "passive"))
      (node (ref "R6") (pin "1") (pinfunction "1_1") (pintype "passive"))
      (node (ref "U2") (pin "15") (pinfunction "GND2_15") (pintype "passive"))
      (node (ref "U2") (pin "9") (pinfunction "GND2_9") (pintype "passive"))
      (node (ref "U3") (pin "2") (pinfunction "GND_2") (pintype "passive"))
      (node (ref "U3") (pin "8") (pinfunction "S_8") (pintype "passive"))
      (node (ref "U4") (pin "4") (pinfunction "Vout-_4") (pintype "passive"))
      (node (ref "X3") (pin "1") (pinfunction "1_1") (pintype "passive"))
    )
    (net (code "56") (name "Net-(U5-AVCC)") (class "Default")
      (node (ref "C13") (pin "2") (pinfunction "2_2") (pintype "passive"))
      (node (ref "R9") (pin "2") (pinfunction "2_2") (pintype "passive"))
      (node (ref "U5") (pin "18") (pinfunction "AVCC_18") (pintype "power_in"))
    )
    (net (code "57") (name "Net-(U6-REF)") (class "Default")
      (node (ref "R15") (pin "1") (pinfunction "1_1") (pintype "passive"))
      (node (ref "R17") (pin "2") (pinfunction "2_2") (pintype "passive"))
      (node (ref "U6") (pin "8") (pinfunction "REF_8") (pintype "input"))
    )
    (net (code "58") (name "Net-(U7-~{RST})") (class "Default")
      (node (ref "JP5") (pin "2") (pinfunction "2_2") (pintype "passive"))
      (node (ref "U7") (pin "1") (pinfunction "~{RST}_1") (pintype "power_in"))
    )
    (net (code "59") (name "Uref") (class "Default")
      (node (ref "C16") (pin "2") (pinfunction "2_2") (pintype "passive"))
      (node (ref "Q1") (pin "3") (pinfunction "E_3") (pintype "passive"))
      (node (ref "R15") (pin "2") (pinfunction "2_2") (pintype "passive"))
      (node (ref "U5") (pin "20") (pinfunction "AREF_20") (pintype "passive"))
    )
    (net (code "60") (name "unconnected-(JP1-Pad8)") (class "Default")
      (node (ref "JP1") (pin "8") (pinfunction "8_8") (pintype "passive"))
    )
    (net (code "61") (name "unconnected-(JP1-Pad18)") (class "Default")
      (node (ref "JP1") (pin "18") (pinfunction "18_18") (pintype "passive"))
    )
    (net (code "62") (name "unconnected-(JP2-Pad2)") (class "Default")
      (node (ref "JP2") (pin "2") (pinfunction "2_2") (pintype "passive"))
    )
    (net (code "63") (name "unconnected-(U1-CLKOUT{slash}SOF-Pad3)") (class "Default")
      (node (ref "U1") (pin "3") (pinfunction "CLKOUT/SOF_3") (pintype "output"))
    )
    (net (code "64") (name "unconnected-(U1-~{RX0BF}-Pad12)") (class "Default")
      (node (ref "U1") (pin "12") (pinfunction "~{RX0BF}_12") (pintype "output"))
    )
    (net (code "65") (name "unconnected-(U1-~{RX1BF}-Pad11)") (class "Default")
      (node (ref "U1") (pin "11") (pinfunction "~{RX1BF}_11") (pintype "output"))
    )
    (net (code "66") (name "unconnected-(U1-~{TX1RTS}-Pad5)") (class "Default")
      (node (ref "U1") (pin "5") (pinfunction "~{TX1RTS}_5") (pintype "input"))
    )
    (net (code "67") (name "unconnected-(U1-~{TX2RTS}-Pad7)") (class "Default")
      (node (ref "U1") (pin "7") (pinfunction "~{TX2RTS}_7") (pintype "input"))
    )
    (net (code "68") (name "unconnected-(U2-InB-Pad4)") (class "Default")
      (node (ref "U2") (pin "4") (pinfunction "InB_4") (pintype "passive"))
    )
    (net (code "69") (name "unconnected-(U2-NC-Pad6)") (class "Default")
      (node (ref "U2") (pin "6") (pinfunction "NC_6") (pintype "passive"))
    )
    (net (code "70") (name "unconnected-(U2-NC-Pad11)") (class "Default")
      (node (ref "U2") (pin "11") (pinfunction "NC_11") (pintype "passive"))
    )
    (net (code "71") (name "unconnected-(U2-OutB-Pad13)") (class "Default")
      (node (ref "U2") (pin "13") (pinfunction "OutB_13") (pintype "passive"))
    )
    (net (code "72") (name "unconnected-(U3-Vref-Pad5)") (class "Default")
      (node (ref "U3") (pin "5") (pinfunction "Vref_5") (pintype "passive"))
    )
    (net (code "73") (name "unconnected-(U5-PB2_(PCINT2{slash}~{SS}{slash}OC1B)-Pad14)") (class "Default")
      (node (ref "U5") (pin "14") (pinfunction "PB2_(PCINT2/~{SS}/OC1B)_14") (pintype "bidirectional"))
    )
    (net (code "74") (name "unconnected-(U6-NC-Pad4)") (class "Default")
      (node (ref "U6") (pin "4") (pinfunction "NC_4") (pintype "passive"))
    )
    (net (code "75") (name "unconnected-(U6-NC-Pad5)") (class "Default")
      (node (ref "U6") (pin "5") (pinfunction "NC_5") (pintype "passive"))
    )
    (net (code "76") (name "unconnected-(U7-~{MR}-Pad3)") (class "Default")
      (node (ref "U7") (pin "3") (pinfunction "~{MR}_3") (pintype "passive"))
    )
  )
)
